# usb2lds_v1_0.net
KiCad netlist of a schematic drawn in EAGLE
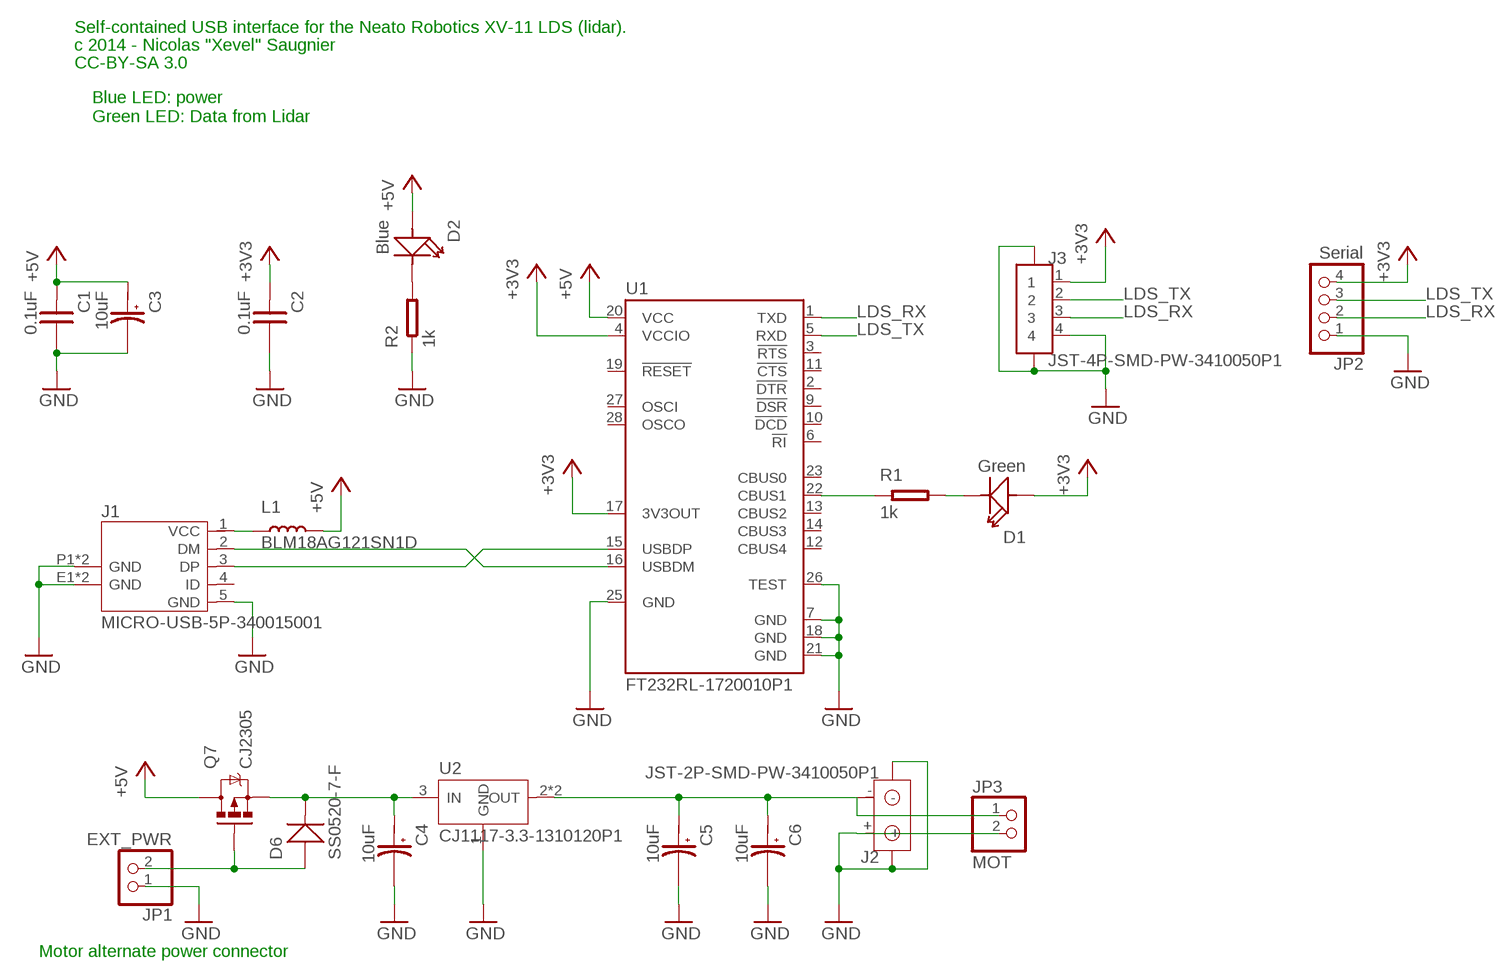
[diagram p0: schematic, sheet 1]

(export (version "E")
  (design (tool "Eeschema 10.0.6"))
  (components
    (comp (ref "C1")
      (value "0.1uF")
      (footprint "eagle-import:C0603")
      (libsource (lib "eagle-import") (part "C-0603"))
    )
    (comp (ref "C2")
      (value "0.1uF")
      (footprint "eagle-import:C0603")
      (libsource (lib "eagle-import") (part "C-0603"))
    )
    (comp (ref "C3")
      (value "10uF")
      (footprint "eagle-import:AVX-A")
      (libsource (lib "eagle-import") (part "C-POLAR-A"))
    )
    (comp (ref "C4")
      (value "10uF")
      (footprint "eagle-import:AVX-A")
      (libsource (lib "eagle-import") (part "C-POLAR-A"))
    )
    (comp (ref "C5")
      (value "10uF")
      (footprint "eagle-import:AVX-A")
      (libsource (lib "eagle-import") (part "C-POLAR-A"))
    )
    (comp (ref "C6")
      (value "10uF")
      (footprint "eagle-import:AVX-A")
      (libsource (lib "eagle-import") (part "C-POLAR-A"))
    )
    (comp (ref "D1")
      (value "Green")
      (footprint "eagle-import:LED0603")
      (libsource (lib "eagle-import") (part "LED"))
    )
    (comp (ref "D2")
      (value "Blue")
      (footprint "eagle-import:LED0603")
      (libsource (lib "eagle-import") (part "LED"))
    )
    (comp (ref "D6")
      (value "SS0520-7-F")
      (footprint "eagle-import:SOD123")
      (libsource (lib "eagle-import") (part "D-SOD-123"))
    )
    (comp (ref "J1")
      (value "MICRO-USB-5P-340015001")
      (footprint "eagle-import:B-SMD-5P")
      (libsource (lib "eagle-import") (part "MICRO-USB-5P-340015001"))
    )
    (comp (ref "J2")
      (value "JST-2P-SMD-PW-3410050P1")
      (footprint "eagle-import:2P-SMD-2.0-90D")
      (libsource (lib "eagle-import") (part "JST-2P-SMD-PW-3410050P1"))
    )
    (comp (ref "J3")
      (value "JST-4P-SMD-PW-3410050P1")
      (footprint "eagle-import:CON-4P-SMD-2.0-90D")
      (libsource (lib "eagle-import") (part "JST-4P-SMD-PW-3410050P1"))
    )
    (comp (ref "JP1")
      (value "EXT_PWR")
      (footprint "eagle-import:1X02")
      (libsource (lib "eagle-import") (part "PINHD-1X2"))
    )
    (comp (ref "JP2")
      (value "Serial")
      (footprint "eagle-import:1X04")
      (libsource (lib "eagle-import") (part "PINHD-1X4"))
    )
    (comp (ref "JP3")
      (value "MOT")
      (footprint "eagle-import:1X02")
      (libsource (lib "eagle-import") (part "PINHD-1X2"))
    )
    (comp (ref "L1")
      (value "BLM18AG121SN1D")
      (footprint "eagle-import:L0603")
      (libsource (lib "eagle-import") (part "L-0603"))
    )
    (comp (ref "Q7")
      (value "CJ2305")
      (footprint "eagle-import:SOT-23-3_N_SSOT-3_N")
      (libsource (lib "eagle-import") (part "MOSFET_P_FDN308P"))
    )
    (comp (ref "R1")
      (value "1k")
      (footprint "eagle-import:R0603")
      (libsource (lib "eagle-import") (part "R-0603"))
    )
    (comp (ref "R2")
      (value "1k")
      (footprint "eagle-import:R0603")
      (libsource (lib "eagle-import") (part "R-0603"))
    )
    (comp (ref "U1")
      (value "FT232RL-1720010P1")
      (footprint "eagle-import:SSOP28")
      (libsource (lib "eagle-import") (part "FT232RL-1720010P1"))
    )
    (comp (ref "U2")
      (value "CJ1117-3.3-1310120P1")
      (footprint "eagle-import:SOT89")
      (libsource (lib "eagle-import") (part "CJ1117-3.3-1310120P1"))
    )
  )
  (nets
    (net (code "1") (name "+3V3") (class "Default")
      (node (ref "C2") (pin "1") (pinfunction "1_1") (pintype "passive"))
      (node (ref "D1") (pin "+") (pinfunction "+_+") (pintype "passive"))
      (node (ref "J3") (pin "1") (pinfunction "1_1") (pintype "bidirectional"))
      (node (ref "JP2") (pin "4") (pinfunction "4_4") (pintype "passive"))
      (node (ref "U1") (pin "17") (pinfunction "3V3OUT_17") (pintype "input"))
      (node (ref "U1") (pin "4") (pinfunction "VCCIO_4") (pintype "input"))
    )
    (net (code "2") (name "+5V") (class "Default")
      (node (ref "C1") (pin "1") (pinfunction "1_1") (pintype "passive"))
      (node (ref "C3") (pin "+") (pinfunction "1_+") (pintype "bidirectional"))
      (node (ref "D2") (pin "+") (pinfunction "+_+") (pintype "passive"))
      (node (ref "L1") (pin "2") (pinfunction "2_2") (pintype "passive"))
      (node (ref "Q7") (pin "3") (pinfunction "D_3") (pintype "passive"))
      (node (ref "U1") (pin "20") (pinfunction "VCC_20") (pintype "input"))
    )
    (net (code "3") (name "/LDS_RX") (class "Default")
      (node (ref "J3") (pin "3") (pinfunction "3_3") (pintype "bidirectional"))
      (node (ref "JP2") (pin "2") (pinfunction "2_2") (pintype "passive"))
      (node (ref "U1") (pin "1") (pinfunction "TXD_1") (pintype "input"))
    )
    (net (code "4") (name "/LDS_TX") (class "Default")
      (node (ref "J3") (pin "2") (pinfunction "2_2") (pintype "bidirectional"))
      (node (ref "JP2") (pin "3") (pinfunction "3_3") (pintype "passive"))
      (node (ref "U1") (pin "5") (pinfunction "RXD_5") (pintype "input"))
    )
    (net (code "5") (name "GND") (class "Default")
      (node (ref "C1") (pin "2") (pinfunction "2_2") (pintype "passive"))
      (node (ref "C2") (pin "2") (pinfunction "2_2") (pintype "passive"))
      (node (ref "C3") (pin "-") (pinfunction "2_-") (pintype "bidirectional"))
      (node (ref "C4") (pin "-") (pinfunction "2_-") (pintype "bidirectional"))
      (node (ref "C5") (pin "-") (pinfunction "2_-") (pintype "bidirectional"))
      (node (ref "C6") (pin "-") (pinfunction "2_-") (pintype "bidirectional"))
      (node (ref "J1") (pin "5") (pinfunction "GND_5") (pintype "bidirectional"))
      (node (ref "J1") (pin "E1") (pinfunction "GND_E1") (pintype "bidirectional"))
      (node (ref "J1") (pin "E2") (pinfunction "GND_E2") (pintype "bidirectional"))
      (node (ref "J1") (pin "P1") (pinfunction "GND_P1") (pintype "bidirectional"))
      (node (ref "J1") (pin "P2") (pinfunction "GND_P2") (pintype "bidirectional"))
      (node (ref "J2") (pin "+") (pinfunction "+_+") (pintype "bidirectional"))
      (node (ref "J2") (pin "3") (pinfunction "3_3") (pintype "bidirectional"))
      (node (ref "J2") (pin "4") (pinfunction "4_4") (pintype "bidirectional"))
      (node (ref "J3") (pin "4") (pinfunction "4_4") (pintype "bidirectional"))
      (node (ref "J3") (pin "5") (pinfunction "5_5") (pintype "bidirectional"))
      (node (ref "J3") (pin "6") (pinfunction "6_6") (pintype "bidirectional"))
      (node (ref "JP1") (pin "1") (pinfunction "1_1") (pintype "passive"))
      (node (ref "JP2") (pin "1") (pinfunction "1_1") (pintype "passive"))
      (node (ref "JP3") (pin "2") (pinfunction "2_2") (pintype "passive"))
      (node (ref "R2") (pin "1") (pinfunction "1_1") (pintype "passive"))
      (node (ref "U1") (pin "18") (pinfunction "GND_18") (pintype "input"))
      (node (ref "U1") (pin "21") (pinfunction "GND_21") (pintype "input"))
      (node (ref "U1") (pin "25") (pinfunction "GND_25") (pintype "input"))
      (node (ref "U1") (pin "26") (pinfunction "TEST_26") (pintype "input"))
      (node (ref "U1") (pin "7") (pinfunction "GND_7") (pintype "input"))
      (node (ref "U2") (pin "1") (pinfunction "GND_1") (pintype "bidirectional"))
    )
    (net (code "6") (name "Net-(C4-1)") (class "Default")
      (node (ref "C4") (pin "+") (pinfunction "1_+") (pintype "bidirectional"))
      (node (ref "D6") (pin "-") (pinfunction "-_-") (pintype "passive"))
      (node (ref "Q7") (pin "2") (pinfunction "S_2") (pintype "passive"))
      (node (ref "U2") (pin "3") (pinfunction "IN_3") (pintype "bidirectional"))
    )
    (net (code "7") (name "Net-(C5-1)") (class "Default")
      (node (ref "C5") (pin "+") (pinfunction "1_+") (pintype "bidirectional"))
      (node (ref "C6") (pin "+") (pinfunction "1_+") (pintype "bidirectional"))
      (node (ref "J2") (pin "-") (pinfunction "-_-") (pintype "bidirectional"))
      (node (ref "JP3") (pin "1") (pinfunction "1_1") (pintype "passive"))
      (node (ref "U2") (pin "2") (pinfunction "OUT_2") (pintype "bidirectional"))
      (node (ref "U2") (pin "4") (pinfunction "OUT_4") (pintype "bidirectional"))
    )
    (net (code "8") (name "Net-(D1-Pad-)") (class "Default")
      (node (ref "D1") (pin "-") (pinfunction "-_-") (pintype "passive"))
      (node (ref "R1") (pin "2") (pinfunction "2_2") (pintype "passive"))
    )
    (net (code "9") (name "Net-(D2-Pad-)") (class "Default")
      (node (ref "D2") (pin "-") (pinfunction "-_-") (pintype "passive"))
      (node (ref "R2") (pin "2") (pinfunction "2_2") (pintype "passive"))
    )
    (net (code "10") (name "Net-(J1-DM)") (class "Default")
      (node (ref "J1") (pin "2") (pinfunction "DM_2") (pintype "bidirectional"))
      (node (ref "U1") (pin "16") (pinfunction "USBDM_16") (pintype "input"))
    )
    (net (code "11") (name "Net-(J1-DP)") (class "Default")
      (node (ref "J1") (pin "3") (pinfunction "DP_3") (pintype "bidirectional"))
      (node (ref "U1") (pin "15") (pinfunction "USBDP_15") (pintype "input"))
    )
    (net (code "12") (name "Net-(J1-VCC)") (class "Default")
      (node (ref "J1") (pin "1") (pinfunction "VCC_1") (pintype "bidirectional"))
      (node (ref "L1") (pin "1") (pinfunction "1_1") (pintype "passive"))
    )
    (net (code "13") (name "Net-(Q7-G)") (class "Default")
      (node (ref "D6") (pin "+") (pinfunction "+_+") (pintype "passive"))
      (node (ref "JP1") (pin "2") (pinfunction "2_2") (pintype "passive"))
      (node (ref "Q7") (pin "1") (pinfunction "G_1") (pintype "passive"))
    )
    (net (code "14") (name "Net-(U1-CBUS1)") (class "Default")
      (node (ref "R1") (pin "1") (pinfunction "1_1") (pintype "passive"))
      (node (ref "U1") (pin "22") (pinfunction "CBUS1_22") (pintype "input"))
    )
    (net (code "15") (name "unconnected-(J1-ID-Pad4)") (class "Default")
      (node (ref "J1") (pin "4") (pinfunction "ID_4") (pintype "bidirectional"))
    )
    (net (code "16") (name "unconnected-(U1-CBUS0-Pad23)") (class "Default")
      (node (ref "U1") (pin "23") (pinfunction "CBUS0_23") (pintype "input"))
    )
    (net (code "17") (name "unconnected-(U1-CBUS2-Pad13)") (class "Default")
      (node (ref "U1") (pin "13") (pinfunction "CBUS2_13") (pintype "input"))
    )
    (net (code "18") (name "unconnected-(U1-CBUS3-Pad14)") (class "Default")
      (node (ref "U1") (pin "14") (pinfunction "CBUS3_14") (pintype "input"))
    )
    (net (code "19") (name "unconnected-(U1-CBUS4-Pad12)") (class "Default")
      (node (ref "U1") (pin "12") (pinfunction "CBUS4_12") (pintype "input"))
    )
    (net (code "20") (name "unconnected-(U1-OSCI-Pad27)") (class "Default")
      (node (ref "U1") (pin "27") (pinfunction "OSCI_27") (pintype "input"))
    )
    (net (code "21") (name "unconnected-(U1-OSCO-Pad28)") (class "Default")
      (node (ref "U1") (pin "28") (pinfunction "OSCO_28") (pintype "input"))
    )
    (net (code "22") (name "unconnected-(U1-~{CTS}-Pad11)") (class "Default")
      (node (ref "U1") (pin "11") (pinfunction "~{CTS}_11") (pintype "input"))
    )
    (net (code "23") (name "unconnected-(U1-~{DCD}-Pad10)") (class "Default")
      (node (ref "U1") (pin "10") (pinfunction "~{DCD}_10") (pintype "input"))
    )
    (net (code "24") (name "unconnected-(U1-~{DSR}-Pad9)") (class "Default")
      (node (ref "U1") (pin "9") (pinfunction "~{DSR}_9") (pintype "input"))
    )
    (net (code "25") (name "unconnected-(U1-~{DTR}-Pad2)") (class "Default")
      (node (ref "U1") (pin "2") (pinfunction "~{DTR}_2") (pintype "input"))
    )
    (net (code "26") (name "unconnected-(U1-~{RESET}-Pad19)") (class "Default")
      (node (ref "U1") (pin "19") (pinfunction "~{RESET}_19") (pintype "input"))
    )
    (net (code "27") (name "unconnected-(U1-~{RI}-Pad6)") (class "Default")
      (node (ref "U1") (pin "6") (pinfunction "~{RI}_6") (pintype "input"))
    )
    (net (code "28") (name "unconnected-(U1-~{RTS}-Pad3)") (class "Default")
      (node (ref "U1") (pin "3") (pinfunction "~{RTS}_3") (pintype "input"))
    )
  )
)
